# SK3000v4.net
KiCad netlist of a schematic drawn in EAGLE
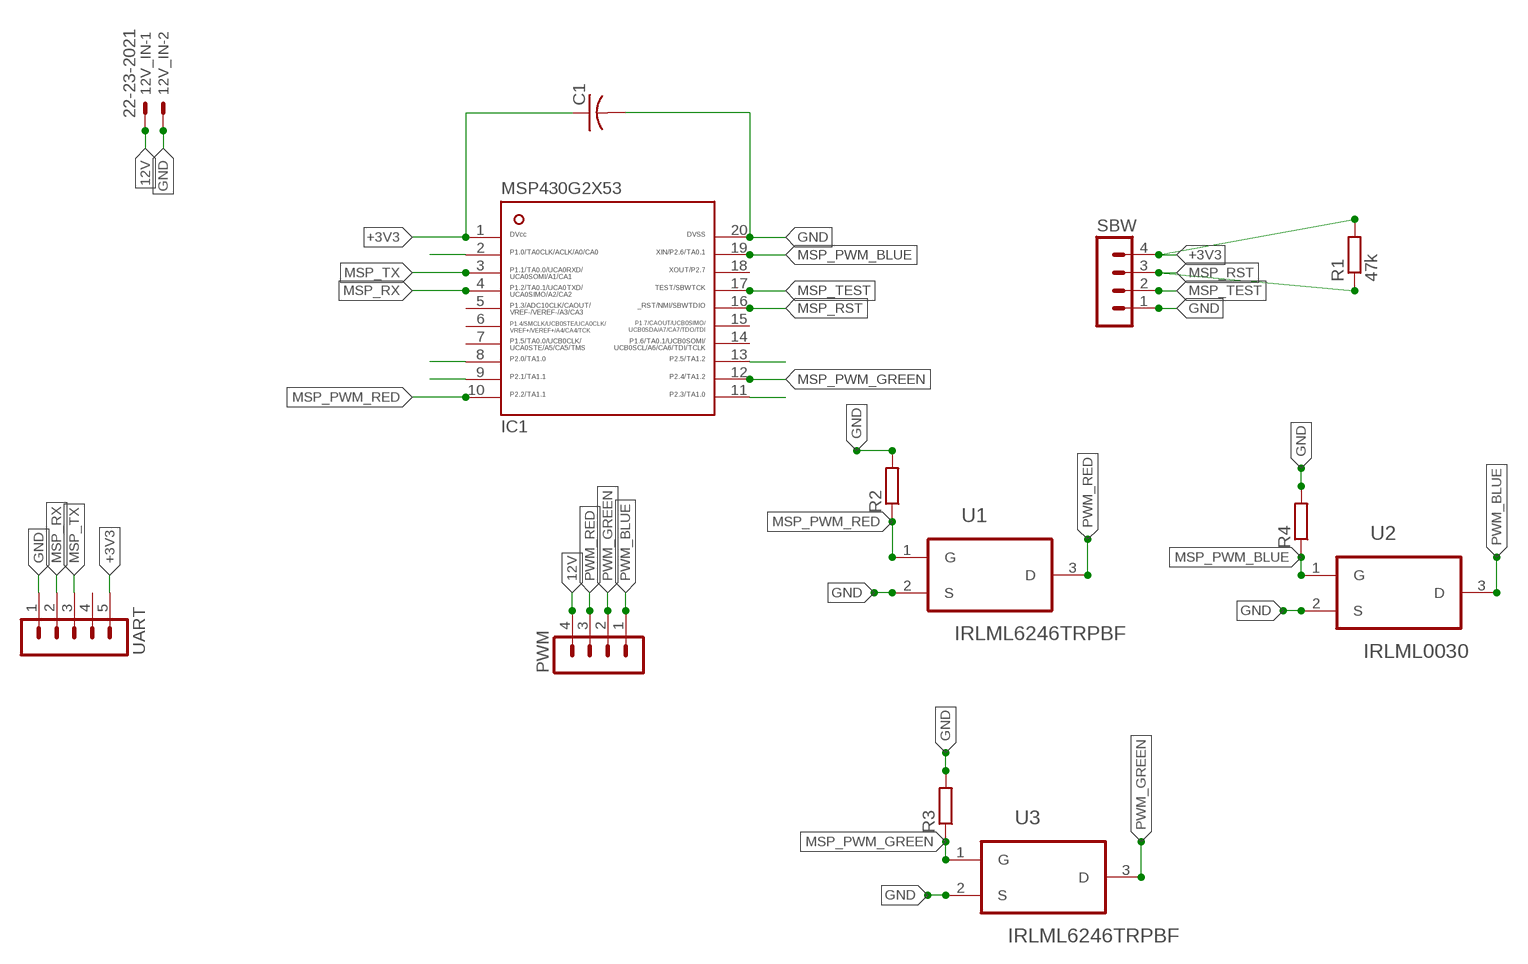
[diagram p0: schematic, sheet 1]

(export (version "E")
  (design (tool "Eeschema 10.0.6"))
  (components
    (comp (ref "12V_IN")
      (value "22-23-2021")
      (footprint "eagle-import:22-23-2021")
      (fields (field (name "MF") "MOLEX"))
      (libsource (lib "eagle-import") (part "22-23-2021"))
    )
    (comp (ref "C1")
      (value "C-USC0603")
      (footprint "eagle-import:C0603")
      (libsource (lib "eagle-import") (part "C-USC0603"))
    )
    (comp (ref "IC1")
      (value "MSP430G2553")
      (footprint "eagle-import:PW20")
      (libsource (lib "eagle-import") (part "MSP430G2X53-20PW20"))
    )
    (comp (ref "PWM")
      (value "MA04-1")
      (footprint "eagle-import:MA04-1")
      (libsource (lib "eagle-import") (part "MA04-1"))
    )
    (comp (ref "R1")
      (value "47k")
      (footprint "eagle-import:R0603")
      (libsource (lib "eagle-import") (part "R-EU_R0603"))
    )
    (comp (ref "R2")
      (value "R-EU_R0603")
      (footprint "eagle-import:R0603")
      (libsource (lib "eagle-import") (part "R-EU_R0603"))
    )
    (comp (ref "R3")
      (value "R-EU_R0603")
      (footprint "eagle-import:R0603")
      (libsource (lib "eagle-import") (part "R-EU_R0603"))
    )
    (comp (ref "R4")
      (value "R-EU_R0603")
      (footprint "eagle-import:R0603")
      (libsource (lib "eagle-import") (part "R-EU_R0603"))
    )
    (comp (ref "SBW")
      (value "MA04-1")
      (footprint "eagle-import:MA04-1")
      (libsource (lib "eagle-import") (part "MA04-1"))
    )
    (comp (ref "U1")
      (value "IRLML6246TRPBF")
      (footprint "eagle-import:SOT95P240X112-3N")
      (libsource (lib "eagle-import") (part "IRLML6246TRPBF"))
    )
    (comp (ref "U2")
      (value "IRLML0030")
      (footprint "eagle-import:SOT95P240X112-3N")
      (fields (field (name "MPN") "IRLML6246TRPBF"))
      (libsource (lib "eagle-import") (part "IRLML6246TRPBF"))
    )
    (comp (ref "U3")
      (value "IRLML6246TRPBF")
      (footprint "eagle-import:SOT95P240X112-3N")
      (libsource (lib "eagle-import") (part "IRLML6246TRPBF"))
    )
    (comp (ref "UART")
      (value "MA05-1")
      (footprint "eagle-import:MA05-1")
      (libsource (lib "eagle-import") (part "MA05-1"))
    )
  )
  (nets
    (net (code "1") (name "+3V3") (class "Default")
      (node (ref "C1") (pin "1") (pinfunction "1_1") (pintype "passive"))
      (node (ref "IC1") (pin "1") (pinfunction "1_1") (pintype "bidirectional"))
      (node (ref "R1") (pin "2") (pinfunction "2_2") (pintype "passive"))
      (node (ref "SBW") (pin "4") (pinfunction "4_4") (pintype "passive"))
      (node (ref "UART") (pin "5") (pinfunction "5_5") (pintype "passive"))
    )
    (net (code "2") (name "12V") (class "Default")
      (node (ref "12V_IN") (pin "1") (pinfunction "S_1") (pintype "passive"))
      (node (ref "PWM") (pin "4") (pinfunction "4_4") (pintype "passive"))
    )
    (net (code "3") (name "GND") (class "Default")
      (node (ref "12V_IN") (pin "2") (pinfunction "S_2") (pintype "passive"))
      (node (ref "C1") (pin "2") (pinfunction "2_2") (pintype "passive"))
      (node (ref "IC1") (pin "20") (pinfunction "20_20") (pintype "bidirectional"))
      (node (ref "R2") (pin "2") (pinfunction "2_2") (pintype "passive"))
      (node (ref "R3") (pin "2") (pinfunction "2_2") (pintype "passive"))
      (node (ref "R4") (pin "2") (pinfunction "2_2") (pintype "passive"))
      (node (ref "SBW") (pin "1") (pinfunction "1_1") (pintype "passive"))
      (node (ref "U1") (pin "2") (pinfunction "S_2") (pintype "passive"))
      (node (ref "U2") (pin "2") (pinfunction "S_2") (pintype "passive"))
      (node (ref "U3") (pin "2") (pinfunction "S_2") (pintype "passive"))
      (node (ref "UART") (pin "1") (pinfunction "1_1") (pintype "passive"))
    )
    (net (code "4") (name "MSP_PWM_BLUE") (class "Default")
      (node (ref "IC1") (pin "19") (pinfunction "19_19") (pintype "bidirectional"))
      (node (ref "R4") (pin "1") (pinfunction "1_1") (pintype "passive"))
      (node (ref "U2") (pin "1") (pinfunction "G_1") (pintype "input"))
    )
    (net (code "5") (name "MSP_PWM_GREEN") (class "Default")
      (node (ref "IC1") (pin "12") (pinfunction "12_12") (pintype "bidirectional"))
      (node (ref "R3") (pin "1") (pinfunction "1_1") (pintype "passive"))
      (node (ref "U3") (pin "1") (pinfunction "G_1") (pintype "input"))
    )
    (net (code "6") (name "MSP_PWM_RED") (class "Default")
      (node (ref "IC1") (pin "10") (pinfunction "10_10") (pintype "bidirectional"))
      (node (ref "R2") (pin "1") (pinfunction "1_1") (pintype "passive"))
      (node (ref "U1") (pin "1") (pinfunction "G_1") (pintype "input"))
    )
    (net (code "7") (name "MSP_RST") (class "Default")
      (node (ref "IC1") (pin "16") (pinfunction "16_16") (pintype "bidirectional"))
      (node (ref "R1") (pin "1") (pinfunction "1_1") (pintype "passive"))
      (node (ref "SBW") (pin "3") (pinfunction "3_3") (pintype "passive"))
    )
    (net (code "8") (name "MSP_RX") (class "Default")
      (node (ref "IC1") (pin "4") (pinfunction "4_4") (pintype "bidirectional"))
      (node (ref "UART") (pin "2") (pinfunction "2_2") (pintype "passive"))
    )
    (net (code "9") (name "MSP_TEST") (class "Default")
      (node (ref "IC1") (pin "17") (pinfunction "17_17") (pintype "bidirectional"))
      (node (ref "SBW") (pin "2") (pinfunction "2_2") (pintype "passive"))
    )
    (net (code "10") (name "MSP_TX") (class "Default")
      (node (ref "IC1") (pin "3") (pinfunction "3_3") (pintype "bidirectional"))
      (node (ref "UART") (pin "3") (pinfunction "3_3") (pintype "passive"))
    )
    (net (code "11") (name "PWM_BLUE") (class "Default")
      (node (ref "PWM") (pin "1") (pinfunction "1_1") (pintype "passive"))
      (node (ref "U2") (pin "3") (pinfunction "D_3") (pintype "output"))
    )
    (net (code "12") (name "PWM_GREEN") (class "Default")
      (node (ref "PWM") (pin "2") (pinfunction "2_2") (pintype "passive"))
      (node (ref "U3") (pin "3") (pinfunction "D_3") (pintype "output"))
    )
    (net (code "13") (name "PWM_RED") (class "Default")
      (node (ref "PWM") (pin "3") (pinfunction "3_3") (pintype "passive"))
      (node (ref "U1") (pin "3") (pinfunction "D_3") (pintype "output"))
    )
    (net (code "14") (name "unconnected-(IC1-Pad2)") (class "Default")
      (node (ref "IC1") (pin "2") (pinfunction "2_2") (pintype "bidirectional"))
    )
    (net (code "15") (name "unconnected-(IC1-Pad5)") (class "Default")
      (node (ref "IC1") (pin "5") (pinfunction "5_5") (pintype "bidirectional"))
    )
    (net (code "16") (name "unconnected-(IC1-Pad6)") (class "Default")
      (node (ref "IC1") (pin "6") (pinfunction "6_6") (pintype "bidirectional"))
    )
    (net (code "17") (name "unconnected-(IC1-Pad7)") (class "Default")
      (node (ref "IC1") (pin "7") (pinfunction "7_7") (pintype "bidirectional"))
    )
    (net (code "18") (name "unconnected-(IC1-Pad8)") (class "Default")
      (node (ref "IC1") (pin "8") (pinfunction "8_8") (pintype "bidirectional"))
    )
    (net (code "19") (name "unconnected-(IC1-Pad9)") (class "Default")
      (node (ref "IC1") (pin "9") (pinfunction "9_9") (pintype "bidirectional"))
    )
    (net (code "20") (name "unconnected-(IC1-Pad11)") (class "Default")
      (node (ref "IC1") (pin "11") (pinfunction "11_11") (pintype "bidirectional"))
    )
    (net (code "21") (name "unconnected-(IC1-Pad13)") (class "Default")
      (node (ref "IC1") (pin "13") (pinfunction "13_13") (pintype "bidirectional"))
    )
    (net (code "22") (name "unconnected-(IC1-Pad14)") (class "Default")
      (node (ref "IC1") (pin "14") (pinfunction "14_14") (pintype "bidirectional"))
    )
    (net (code "23") (name "unconnected-(IC1-Pad15)") (class "Default")
      (node (ref "IC1") (pin "15") (pinfunction "15_15") (pintype "bidirectional"))
    )
    (net (code "24") (name "unconnected-(IC1-Pad18)") (class "Default")
      (node (ref "IC1") (pin "18") (pinfunction "18_18") (pintype "bidirectional"))
    )
    (net (code "25") (name "unconnected-(UART-Pad4)") (class "Default")
      (node (ref "UART") (pin "4") (pinfunction "4_4") (pintype "passive"))
    )
  )
)
